# 01_MAIN.net
KiCad netlist of a schematic drawn in Altium Designer
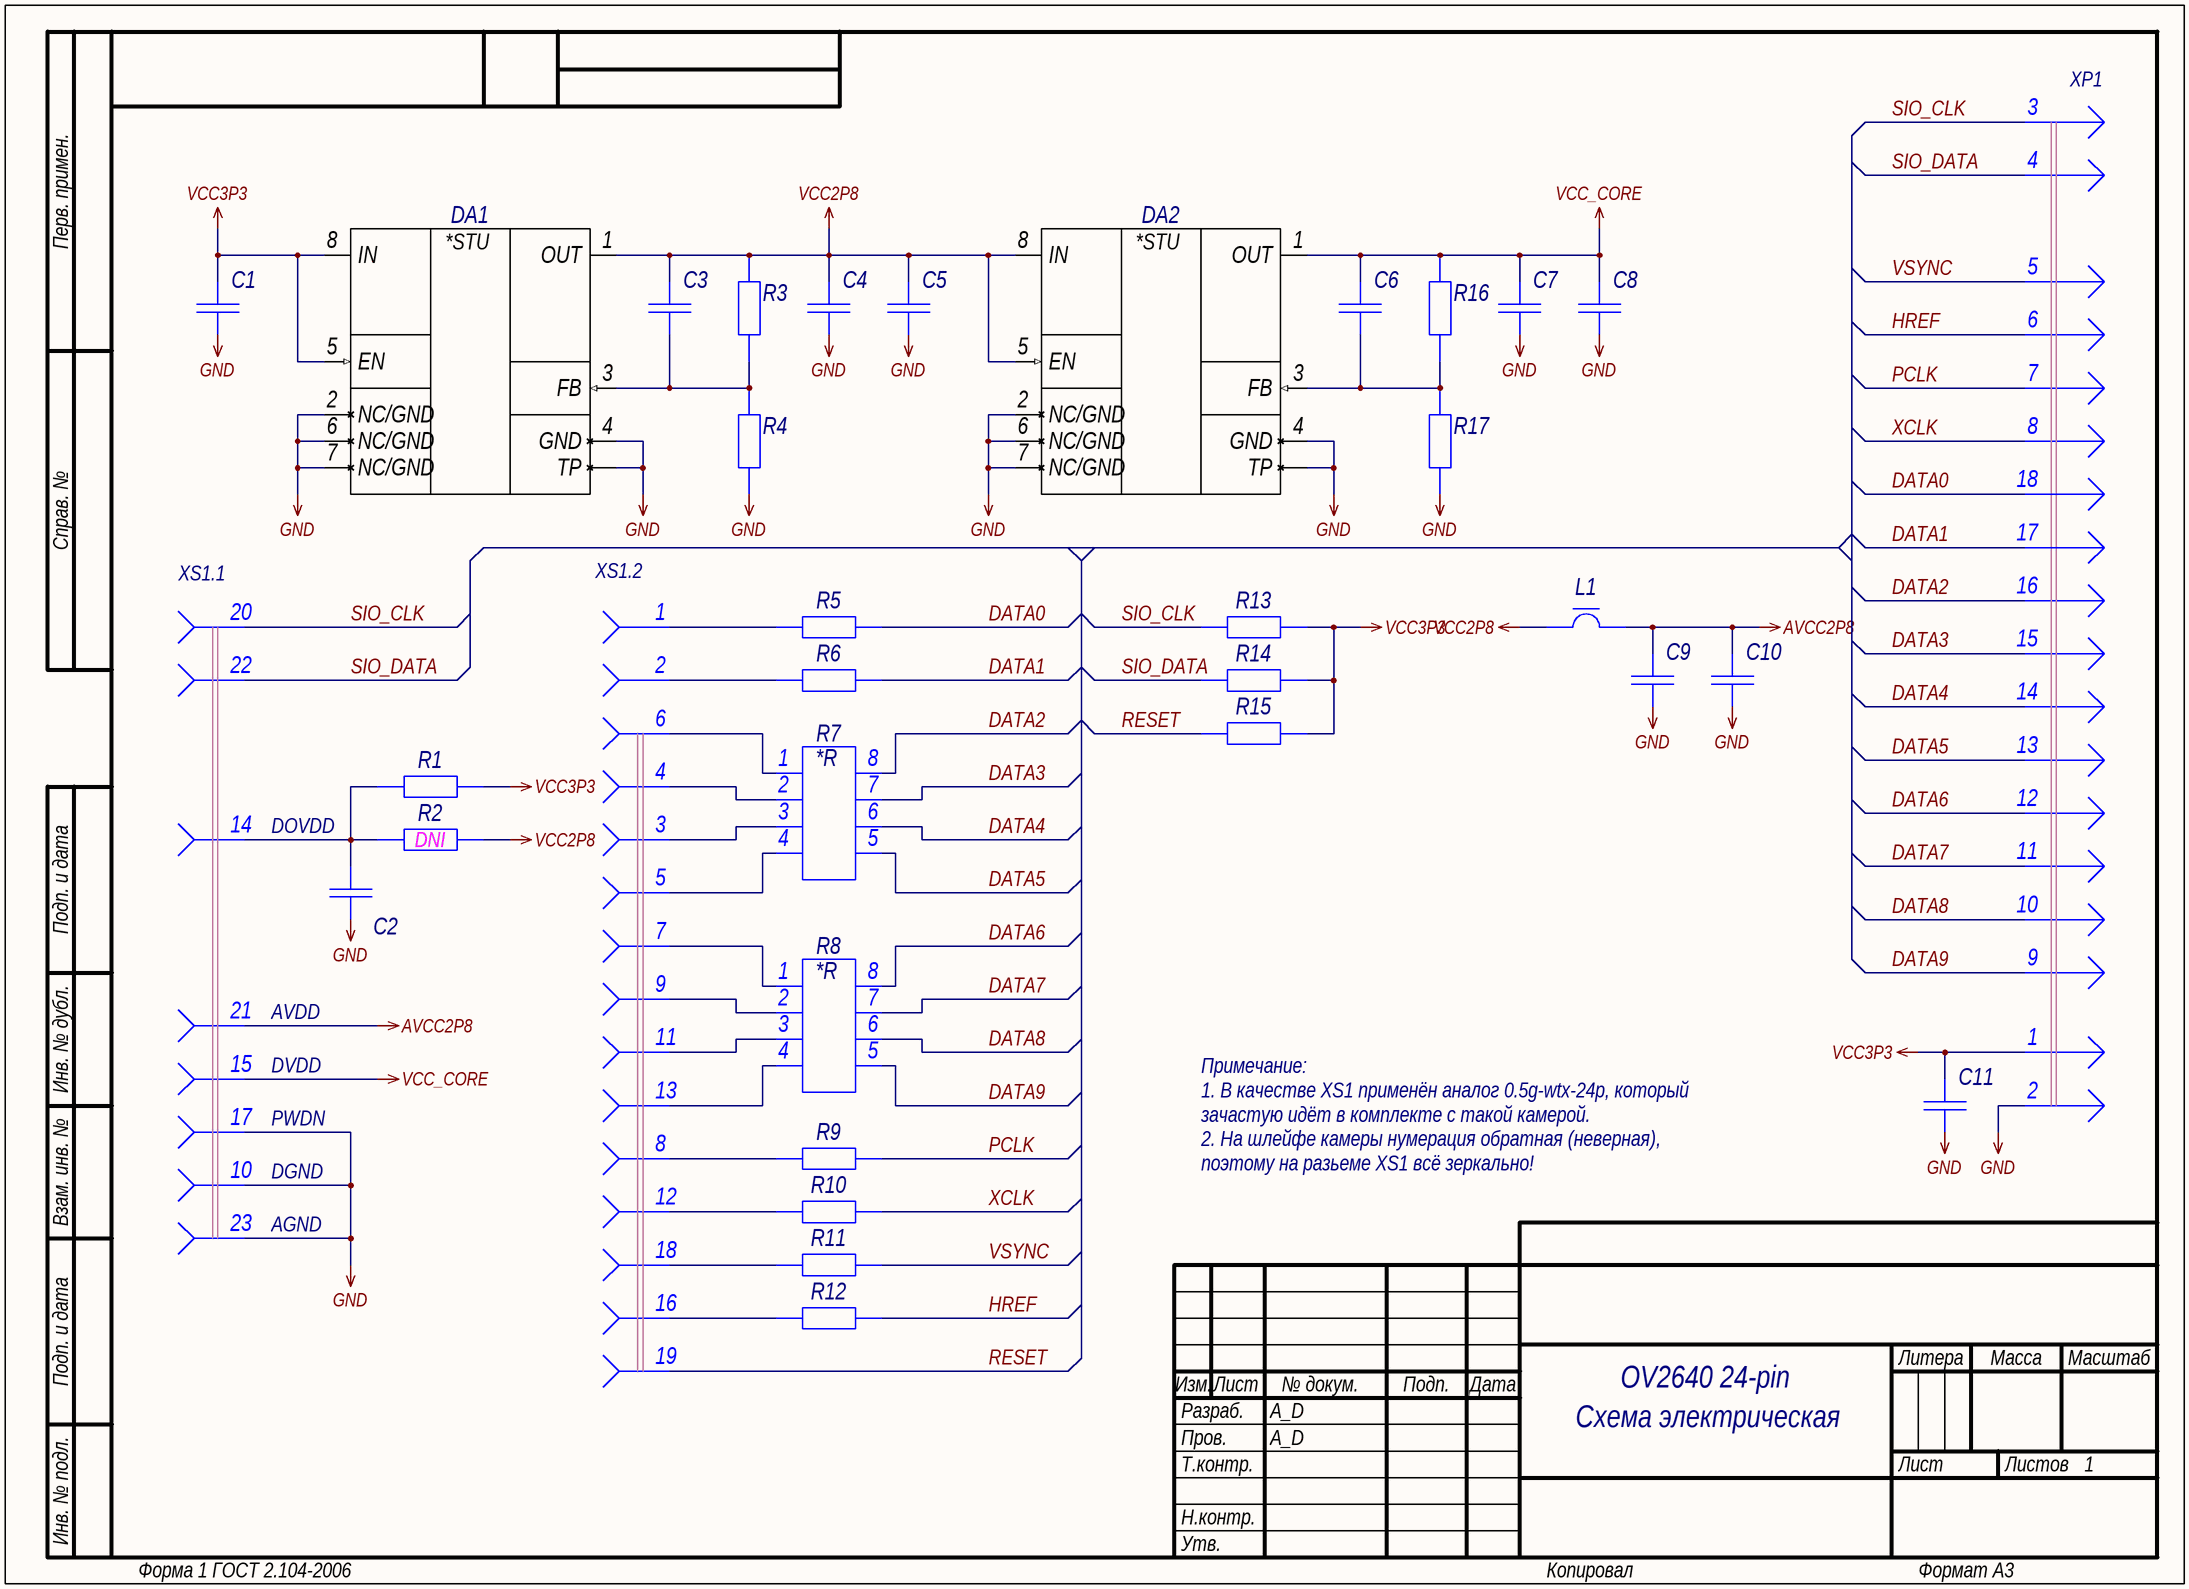
[diagram p0: 01_MAIN.SchDoc]

(export (version "E")
  (design (tool "Eeschema 10.0.6"))
  (components
    (comp (ref "C1")
      (value "Capacitor")
      (footprint "C0603_160X080H080_H")
      (fields
        (field (name "PART NUMBER") "GCM188R71E105KA64D")
        (field (name "VOLTAGE") "25V")
        (field (name "TOLERANCE") "±10%")
        (field (name "PUBLISHER") "Andrew Danich")
      )
      (libsource (lib "ADLib") (part "Capacitor"))
    )
    (comp (ref "C2")
      (value "Capacitor")
      (footprint "C0603_160X080H080_H")
      (fields
        (field (name "PART NUMBER") "GCM188R71E105KA64D")
        (field (name "VOLTAGE") "25V")
        (field (name "TOLERANCE") "±10%")
        (field (name "PUBLISHER") "Andrew Danich")
      )
      (libsource (lib "ADLib") (part "Capacitor"))
    )
    (comp (ref "C3")
      (value "Capacitor")
      (footprint "C0603_160X080H080_H")
      (fields
        (field (name "PART NUMBER") "GRM1885C1H270JA01D")
        (field (name "VOLTAGE") "50V")
        (field (name "TOLERANCE") "±5%")
        (field (name "PUBLISHER") "Andrew Danich")
      )
      (libsource (lib "ADLib") (part "Capacitor"))
    )
    (comp (ref "C4")
      (value "Capacitor")
      (footprint "C0603_160X080H080_H")
      (fields
        (field (name "PART NUMBER") "GRM188R60J106ME47D")
        (field (name "VOLTAGE") "6.3V")
        (field (name "TOLERANCE") "±20%")
        (field (name "PUBLISHER") "Andrew Danich")
      )
      (libsource (lib "ADLib") (part "Capacitor"))
    )
    (comp (ref "C5")
      (value "Capacitor")
      (footprint "C0603_160X080H080_H")
      (fields
        (field (name "PART NUMBER") "GCM188R71E105KA64D")
        (field (name "VOLTAGE") "25V")
        (field (name "TOLERANCE") "±10%")
        (field (name "PUBLISHER") "Andrew Danich")
      )
      (libsource (lib "ADLib") (part "Capacitor"))
    )
    (comp (ref "C6")
      (value "Capacitor")
      (footprint "C0603_160X080H080_H")
      (fields
        (field (name "PART NUMBER") "GRM1885C1H270JA01D")
        (field (name "VOLTAGE") "50V")
        (field (name "TOLERANCE") "±5%")
        (field (name "PUBLISHER") "Andrew Danich")
      )
      (libsource (lib "ADLib") (part "Capacitor"))
    )
    (comp (ref "C7")
      (value "Capacitor")
      (footprint "C0603_160X080H080_H")
      (fields
        (field (name "PART NUMBER") "GRM188R60J106ME47D")
        (field (name "VOLTAGE") "6.3V")
        (field (name "TOLERANCE") "±20%")
        (field (name "PUBLISHER") "Andrew Danich")
      )
      (libsource (lib "ADLib") (part "Capacitor"))
    )
    (comp (ref "C8")
      (value "Capacitor")
      (footprint "C0603_160X080H080_H")
      (fields
        (field (name "PART NUMBER") "GRM188R72A104KA35D")
        (field (name "VOLTAGE") "100V")
        (field (name "TOLERANCE") "±10%")
        (field (name "PUBLISHER") "Andrew Danich")
      )
      (libsource (lib "ADLib") (part "Capacitor"))
    )
    (comp (ref "C9")
      (value "Capacitor")
      (footprint "C0603_160X080H080_H")
      (fields
        (field (name "PART NUMBER") "GCM188R71E105KA64D")
        (field (name "VOLTAGE") "25V")
        (field (name "TOLERANCE") "±10%")
        (field (name "PUBLISHER") "Andrew Danich")
      )
      (libsource (lib "ADLib") (part "Capacitor"))
    )
    (comp (ref "C10")
      (value "Capacitor")
      (footprint "C0603_160X080H080_H")
      (fields
        (field (name "PART NUMBER") "GRM188R72A104KA35D")
        (field (name "VOLTAGE") "100V")
        (field (name "TOLERANCE") "±10%")
        (field (name "PUBLISHER") "Andrew Danich")
      )
      (libsource (lib "ADLib") (part "Capacitor"))
    )
    (comp (ref "C11")
      (value "Capacitor")
      (footprint "C0603_160X080H080_H")
      (fields
        (field (name "PART NUMBER") "GRM188R60J106ME47D")
        (field (name "VOLTAGE") "6.3V")
        (field (name "TOLERANCE") "±20%")
        (field (name "PUBLISHER") "Andrew Danich")
      )
      (libsource (lib "ADLib") (part "Capacitor"))
    )
    (comp (ref "DA1")
      (value "TPS73501DRB")
      (footprint "VSON-8_065P300X300X100_N")
      (fields
        (field (name "PART NUMBER") "TPS73501DRBR")
        (field (name "MANUFACTURER") "Texas Instruments")
        (field (name "PUBLISHER") "Andrew Danich")
      )
      (libsource (lib "ADLib") (part "TPS73501DRB"))
    )
    (comp (ref "DA2")
      (value "TPS73501DRB")
      (footprint "VSON-8_065P300X300X100_N")
      (fields
        (field (name "PART NUMBER") "TPS73501DRBR")
        (field (name "MANUFACTURER") "Texas Instruments")
        (field (name "PUBLISHER") "Andrew Danich")
      )
      (libsource (lib "ADLib") (part "TPS73501DRB"))
    )
    (comp (ref "L1")
      (value "FerriteBead")
      (footprint "L0603_160X080H080_H")
      (fields
        (field (name "PART NUMBER") "BLM18PG221SH1D")
        (field (name "TOLERANCE") "±25%")
        (field (name "MANUFACTURER") "Murata")
        (field (name "PUBLISHER") "Andrew Danich")
      )
      (libsource (lib "ADLib") (part "FerriteBead"))
    )
    (comp (ref "R1")
      (value "Resistor")
      (footprint "R0603_160X080H045_H")
      (fields
        (field (name "PART NUMBER") "RC0603JR-070R")
        (field (name "TOLERANCE") "±5%")
        (field (name "MANUFACTURER") "Yageo")
        (field (name "PUBLISHER") "Andrew Danich")
      )
      (libsource (lib "ADLib") (part "Resistor"))
    )
    (comp (ref "R2")
      (value "Resistor")
      (footprint "R0603_160X080H045_H")
      (fields
        (field (name "PART NUMBER") "RC0603JR-070R")
        (field (name "TOLERANCE") "±5%")
        (field (name "MANUFACTURER") "Yageo")
        (field (name "PUBLISHER") "Andrew Danich")
      )
      (libsource (lib "ADLib") (part "Resistor"))
    )
    (comp (ref "R3")
      (value "Resistor")
      (footprint "R0603_160X080H045_H")
      (fields
        (field (name "PART NUMBER") "RC0603JR-0727KL")
        (field (name "TOLERANCE") "±5%")
        (field (name "MANUFACTURER") "Yageo")
        (field (name "PUBLISHER") "Andrew Danich")
      )
      (libsource (lib "ADLib") (part "Resistor"))
    )
    (comp (ref "R4")
      (value "Resistor")
      (footprint "R0603_160X080H045_H")
      (fields
        (field (name "PART NUMBER") "RC0603FR-0720KL")
        (field (name "TOLERANCE") "±1%")
        (field (name "MANUFACTURER") "Yageo")
        (field (name "PUBLISHER") "Andrew Danich")
      )
      (libsource (lib "ADLib") (part "Resistor"))
    )
    (comp (ref "R5")
      (value "Resistor")
      (footprint "R0603_160X080H045_H")
      (fields
        (field (name "PART NUMBER") "RC0603JR-0751RL")
        (field (name "TOLERANCE") "±5%")
        (field (name "MANUFACTURER") "Yageo")
        (field (name "PUBLISHER") "Andrew Danich")
      )
      (libsource (lib "ADLib") (part "Resistor"))
    )
    (comp (ref "R6")
      (value "Resistor")
      (footprint "R0603_160X080H045_H")
      (fields
        (field (name "PART NUMBER") "RC0603JR-0751RL")
        (field (name "TOLERANCE") "±5%")
        (field (name "MANUFACTURER") "Yageo")
        (field (name "PUBLISHER") "Andrew Danich")
      )
      (libsource (lib "ADLib") (part "Resistor"))
    )
    (comp (ref "R7")
      (value "Resistor-4")
      (footprint "CAT16-x4")
      (fields
        (field (name "PART NUMBER") "CAT16-510J4LF")
        (field (name "TOLERANCE") "±5%")
        (field (name "MANUFACTURER") "Bourns")
        (field (name "PUBLISHER") "Andrew Danich")
      )
      (libsource (lib "ADLib") (part "Resistor-4"))
    )
    (comp (ref "R8")
      (value "Resistor-4")
      (footprint "CAT16-x4")
      (fields
        (field (name "PART NUMBER") "CAT16-510J4LF")
        (field (name "TOLERANCE") "±5%")
        (field (name "MANUFACTURER") "Bourns")
        (field (name "PUBLISHER") "Andrew Danich")
      )
      (libsource (lib "ADLib") (part "Resistor-4"))
    )
    (comp (ref "R9")
      (value "Resistor")
      (footprint "R0603_160X080H045_H")
      (fields
        (field (name "PART NUMBER") "RC0603JR-0751RL")
        (field (name "TOLERANCE") "±5%")
        (field (name "MANUFACTURER") "Yageo")
        (field (name "PUBLISHER") "Andrew Danich")
      )
      (libsource (lib "ADLib") (part "Resistor"))
    )
    (comp (ref "R10")
      (value "Resistor")
      (footprint "R0603_160X080H045_H")
      (fields
        (field (name "PART NUMBER") "RC0603JR-0751RL")
        (field (name "TOLERANCE") "±5%")
        (field (name "MANUFACTURER") "Yageo")
        (field (name "PUBLISHER") "Andrew Danich")
      )
      (libsource (lib "ADLib") (part "Resistor"))
    )
    (comp (ref "R11")
      (value "Resistor")
      (footprint "R0603_160X080H045_H")
      (fields
        (field (name "PART NUMBER") "RC0603JR-0751RL")
        (field (name "TOLERANCE") "±5%")
        (field (name "MANUFACTURER") "Yageo")
        (field (name "PUBLISHER") "Andrew Danich")
      )
      (libsource (lib "ADLib") (part "Resistor"))
    )
    (comp (ref "R12")
      (value "Resistor")
      (footprint "R0603_160X080H045_H")
      (fields
        (field (name "PART NUMBER") "RC0603JR-0751RL")
        (field (name "TOLERANCE") "±5%")
        (field (name "MANUFACTURER") "Yageo")
        (field (name "PUBLISHER") "Andrew Danich")
      )
      (libsource (lib "ADLib") (part "Resistor"))
    )
    (comp (ref "R13")
      (value "Resistor")
      (footprint "R0603_160X080H045_H")
      (fields
        (field (name "PART NUMBER") "RC0603JR-074K7L")
        (field (name "TOLERANCE") "±5%")
        (field (name "MANUFACTURER") "Yageo")
        (field (name "PUBLISHER") "Andrew Danich")
      )
      (libsource (lib "ADLib") (part "Resistor"))
    )
    (comp (ref "R14")
      (value "Resistor")
      (footprint "R0603_160X080H045_H")
      (fields
        (field (name "PART NUMBER") "RC0603JR-074K7L")
        (field (name "TOLERANCE") "±5%")
        (field (name "MANUFACTURER") "Yageo")
        (field (name "PUBLISHER") "Andrew Danich")
      )
      (libsource (lib "ADLib") (part "Resistor"))
    )
    (comp (ref "R15")
      (value "Resistor")
      (footprint "R0603_160X080H045_H")
      (fields
        (field (name "PART NUMBER") "RC0603JR-074K7L")
        (field (name "TOLERANCE") "±5%")
        (field (name "MANUFACTURER") "Yageo")
        (field (name "PUBLISHER") "Andrew Danich")
      )
      (libsource (lib "ADLib") (part "Resistor"))
    )
    (comp (ref "R16")
      (value "Resistor")
      (footprint "R0603_160X080H045_H")
      (fields
        (field (name "PART NUMBER") "RC0603JR-0727KL")
        (field (name "TOLERANCE") "±5%")
        (field (name "MANUFACTURER") "Yageo")
        (field (name "PUBLISHER") "Andrew Danich")
      )
      (libsource (lib "ADLib") (part "Resistor"))
    )
    (comp (ref "R17")
      (value "Resistor")
      (footprint "R0603_160X080H045_H")
      (fields
        (field (name "PART NUMBER") "RC0603JR-07360KL")
        (field (name "TOLERANCE") "±5%")
        (field (name "MANUFACTURER") "Yageo")
        (field (name "PUBLISHER") "Andrew Danich")
      )
      (libsource (lib "ADLib") (part "Resistor"))
    )
    (comp (ref "XP1")
      (value "Text")
      (footprint "PLD-18")
      (fields (field (name "PART NUMBER") "PLD-18") (field (name "PUBLISHER") "Andrew Danich"))
      (libsource (lib "ADLib") (part "Con-18-M_S"))
    )
    (comp (ref "XS1")
      (value "OV7670")
      (footprint "FH12-24S-0.5SH")
      (fields
        (field (name "PART NUMBER") "FH12-24S-0.5SH(55)")
        (field (name "MANUFACTURER") "Hirose Connector")
        (field (name "PUBLISHER") "Andrew Danich")
      )
      (libsource (lib "ADLib") (part "Con-24-F_S"))
    )
  )
  (nets
    (net (code "1") (name "/DATA0") (class "Default")
      (node (ref "R5") (pin "2") (pinfunction "2_2") (pintype "passive"))
      (node (ref "XP1") (pin "18") (pintype "passive"))
    )
    (net (code "2") (name "/DATA1") (class "Default")
      (node (ref "R6") (pin "2") (pinfunction "2_2") (pintype "passive"))
      (node (ref "XP1") (pin "17") (pintype "passive"))
    )
    (net (code "3") (name "/DATA2") (class "Default")
      (node (ref "R7") (pin "8") (pintype "passive"))
      (node (ref "XP1") (pin "16") (pintype "passive"))
    )
    (net (code "4") (name "/DATA3") (class "Default")
      (node (ref "R7") (pin "7") (pintype "passive"))
      (node (ref "XP1") (pin "15") (pintype "passive"))
    )
    (net (code "5") (name "/DATA4") (class "Default")
      (node (ref "R7") (pin "6") (pintype "passive"))
      (node (ref "XP1") (pin "14") (pintype "passive"))
    )
    (net (code "6") (name "/DATA5") (class "Default")
      (node (ref "R7") (pin "5") (pintype "passive"))
      (node (ref "XP1") (pin "13") (pintype "passive"))
    )
    (net (code "7") (name "/DATA6") (class "Default")
      (node (ref "R8") (pin "8") (pintype "passive"))
      (node (ref "XP1") (pin "12") (pintype "passive"))
    )
    (net (code "8") (name "/DATA7") (class "Default")
      (node (ref "R8") (pin "7") (pintype "passive"))
      (node (ref "XP1") (pin "11") (pintype "passive"))
    )
    (net (code "9") (name "/DATA8") (class "Default")
      (node (ref "R8") (pin "6") (pintype "passive"))
      (node (ref "XP1") (pin "10") (pintype "passive"))
    )
    (net (code "10") (name "/DATA9") (class "Default")
      (node (ref "R8") (pin "5") (pintype "passive"))
      (node (ref "XP1") (pin "9") (pintype "passive"))
    )
    (net (code "11") (name "/HREF") (class "Default")
      (node (ref "R12") (pin "2") (pinfunction "2_2") (pintype "passive"))
      (node (ref "XP1") (pin "6") (pintype "passive"))
    )
    (net (code "12") (name "/PCLK") (class "Default")
      (node (ref "R9") (pin "2") (pinfunction "2_2") (pintype "passive"))
      (node (ref "XP1") (pin "7") (pintype "passive"))
    )
    (net (code "13") (name "/RESET") (class "Default")
      (node (ref "R15") (pin "1") (pinfunction "1_1") (pintype "passive"))
      (node (ref "XS1") (pin "19") (pintype "passive"))
    )
    (net (code "14") (name "/SIO_CLK") (class "Default")
      (node (ref "R13") (pin "1") (pinfunction "1_1") (pintype "passive"))
      (node (ref "XP1") (pin "3") (pintype "passive"))
      (node (ref "XS1") (pin "20") (pintype "passive"))
    )
    (net (code "15") (name "/SIO_DATA") (class "Default")
      (node (ref "R14") (pin "1") (pinfunction "1_1") (pintype "passive"))
      (node (ref "XP1") (pin "4") (pintype "passive"))
      (node (ref "XS1") (pin "22") (pintype "passive"))
    )
    (net (code "16") (name "/VSYNC") (class "Default")
      (node (ref "R11") (pin "2") (pinfunction "2_2") (pintype "passive"))
      (node (ref "XP1") (pin "5") (pintype "passive"))
    )
    (net (code "17") (name "/XCLK") (class "Default")
      (node (ref "R10") (pin "2") (pinfunction "2_2") (pintype "passive"))
      (node (ref "XP1") (pin "8") (pintype "passive"))
    )
    (net (code "18") (name "AVCC2P8") (class "Default")
      (node (ref "C10") (pin "2") (pinfunction "2_2") (pintype "passive"))
      (node (ref "C9") (pin "2") (pinfunction "2_2") (pintype "passive"))
      (node (ref "L1") (pin "2") (pinfunction "2_2") (pintype "passive"))
      (node (ref "XS1") (pin "21") (pintype "passive"))
    )
    (net (code "19") (name "GND") (class "Default")
      (node (ref "C1") (pin "1") (pinfunction "1_1") (pintype "passive"))
      (node (ref "C10") (pin "1") (pinfunction "1_1") (pintype "passive"))
      (node (ref "C11") (pin "1") (pinfunction "1_1") (pintype "passive"))
      (node (ref "C2") (pin "1") (pinfunction "1_1") (pintype "passive"))
      (node (ref "C4") (pin "1") (pinfunction "1_1") (pintype "passive"))
      (node (ref "C5") (pin "1") (pinfunction "1_1") (pintype "passive"))
      (node (ref "C7") (pin "1") (pinfunction "1_1") (pintype "passive"))
      (node (ref "C8") (pin "1") (pinfunction "1_1") (pintype "passive"))
      (node (ref "C9") (pin "1") (pinfunction "1_1") (pintype "passive"))
      (node (ref "DA1") (pin "2") (pinfunction "NC/GND_2") (pintype "passive"))
      (node (ref "DA1") (pin "4") (pinfunction "GND_4") (pintype "power_in"))
      (node (ref "DA1") (pin "6") (pinfunction "NC/GND_6") (pintype "passive"))
      (node (ref "DA1") (pin "7") (pinfunction "NC/GND_7") (pintype "passive"))
      (node (ref "DA1") (pin "TP") (pinfunction "TP_TP") (pintype "passive"))
      (node (ref "DA2") (pin "2") (pinfunction "NC/GND_2") (pintype "passive"))
      (node (ref "DA2") (pin "4") (pinfunction "GND_4") (pintype "power_in"))
      (node (ref "DA2") (pin "6") (pinfunction "NC/GND_6") (pintype "passive"))
      (node (ref "DA2") (pin "7") (pinfunction "NC/GND_7") (pintype "passive"))
      (node (ref "DA2") (pin "TP") (pinfunction "TP_TP") (pintype "passive"))
      (node (ref "R17") (pin "1") (pinfunction "1_1") (pintype "passive"))
      (node (ref "R4") (pin "1") (pinfunction "1_1") (pintype "passive"))
      (node (ref "XP1") (pin "2") (pintype "passive"))
      (node (ref "XS1") (pin "10") (pintype "passive"))
      (node (ref "XS1") (pin "17") (pintype "passive"))
      (node (ref "XS1") (pin "23") (pintype "passive"))
    )
    (net (code "20") (name "Net-(C2-Pad2)") (class "Default")
      (node (ref "C2") (pin "2") (pinfunction "2_2") (pintype "passive"))
      (node (ref "R1") (pin "1") (pinfunction "1_1") (pintype "passive"))
      (node (ref "R2") (pin "1") (pinfunction "1_1") (pintype "passive"))
      (node (ref "XS1") (pin "14") (pintype "passive"))
    )
    (net (code "21") (name "Net-(DA1-FB)") (class "Default")
      (node (ref "C3") (pin "1") (pinfunction "1_1") (pintype "passive"))
      (node (ref "DA1") (pin "3") (pinfunction "FB_3") (pintype "input"))
      (node (ref "R3") (pin "2") (pinfunction "2_2") (pintype "passive"))
      (node (ref "R4") (pin "2") (pinfunction "2_2") (pintype "passive"))
    )
    (net (code "22") (name "Net-(DA2-FB)") (class "Default")
      (node (ref "C6") (pin "1") (pinfunction "1_1") (pintype "passive"))
      (node (ref "DA2") (pin "3") (pinfunction "FB_3") (pintype "input"))
      (node (ref "R16") (pin "1") (pinfunction "1_1") (pintype "passive"))
      (node (ref "R17") (pin "2") (pinfunction "2_2") (pintype "passive"))
    )
    (net (code "23") (name "Net-(R5-Pad1)") (class "Default")
      (node (ref "R5") (pin "1") (pinfunction "1_1") (pintype "passive"))
      (node (ref "XS1") (pin "1") (pintype "passive"))
    )
    (net (code "24") (name "Net-(R6-Pad1)") (class "Default")
      (node (ref "R6") (pin "1") (pinfunction "1_1") (pintype "passive"))
      (node (ref "XS1") (pin "2") (pintype "passive"))
    )
    (net (code "25") (name "Net-(R7-Pad1)") (class "Default")
      (node (ref "R7") (pin "1") (pintype "passive"))
      (node (ref "XS1") (pin "6") (pintype "passive"))
    )
    (net (code "26") (name "Net-(R7-Pad2)") (class "Default")
      (node (ref "R7") (pin "2") (pintype "passive"))
      (node (ref "XS1") (pin "4") (pintype "passive"))
    )
    (net (code "27") (name "Net-(R7-Pad3)") (class "Default")
      (node (ref "R7") (pin "3") (pintype "passive"))
      (node (ref "XS1") (pin "3") (pintype "passive"))
    )
    (net (code "28") (name "Net-(R7-Pad4)") (class "Default")
      (node (ref "R7") (pin "4") (pintype "passive"))
      (node (ref "XS1") (pin "5") (pintype "passive"))
    )
    (net (code "29") (name "Net-(R8-Pad1)") (class "Default")
      (node (ref "R8") (pin "1") (pintype "passive"))
      (node (ref "XS1") (pin "7") (pintype "passive"))
    )
    (net (code "30") (name "Net-(R8-Pad2)") (class "Default")
      (node (ref "R8") (pin "2") (pintype "passive"))
      (node (ref "XS1") (pin "9") (pintype "passive"))
    )
    (net (code "31") (name "Net-(R8-Pad3)") (class "Default")
      (node (ref "R8") (pin "3") (pintype "passive"))
      (node (ref "XS1") (pin "11") (pintype "passive"))
    )
    (net (code "32") (name "Net-(R8-Pad4)") (class "Default")
      (node (ref "R8") (pin "4") (pintype "passive"))
      (node (ref "XS1") (pin "13") (pintype "passive"))
    )
    (net (code "33") (name "Net-(R9-Pad1)") (class "Default")
      (node (ref "R9") (pin "1") (pinfunction "1_1") (pintype "passive"))
      (node (ref "XS1") (pin "8") (pintype "passive"))
    )
    (net (code "34") (name "Net-(R10-Pad1)") (class "Default")
      (node (ref "R10") (pin "1") (pinfunction "1_1") (pintype "passive"))
      (node (ref "XS1") (pin "12") (pintype "passive"))
    )
    (net (code "35") (name "Net-(R11-Pad1)") (class "Default")
      (node (ref "R11") (pin "1") (pinfunction "1_1") (pintype "passive"))
      (node (ref "XS1") (pin "18") (pintype "passive"))
    )
    (net (code "36") (name "Net-(R12-Pad1)") (class "Default")
      (node (ref "R12") (pin "1") (pinfunction "1_1") (pintype "passive"))
      (node (ref "XS1") (pin "16") (pintype "passive"))
    )
    (net (code "37") (name "VCC2P8") (class "Default")
      (node (ref "C3") (pin "2") (pinfunction "2_2") (pintype "passive"))
      (node (ref "C4") (pin "2") (pinfunction "2_2") (pintype "passive"))
      (node (ref "C5") (pin "2") (pinfunction "2_2") (pintype "passive"))
      (node (ref "DA1") (pin "1") (pinfunction "OUT_1") (pintype "power_in"))
      (node (ref "DA2") (pin "5") (pinfunction "EN_5") (pintype "input"))
      (node (ref "DA2") (pin "8") (pinfunction "IN_8") (pintype "power_in"))
      (node (ref "L1") (pin "1") (pinfunction "1_1") (pintype "passive"))
      (node (ref "R2") (pin "2") (pinfunction "2_2") (pintype "passive"))
      (node (ref "R3") (pin "1") (pinfunction "1_1") (pintype "passive"))
    )
    (net (code "38") (name "VCC3P3") (class "Default")
      (node (ref "C1") (pin "2") (pinfunction "2_2") (pintype "passive"))
      (node (ref "C11") (pin "2") (pinfunction "2_2") (pintype "passive"))
      (node (ref "DA1") (pin "5") (pinfunction "EN_5") (pintype "input"))
      (node (ref "DA1") (pin "8") (pinfunction "IN_8") (pintype "power_in"))
      (node (ref "R1") (pin "2") (pinfunction "2_2") (pintype "passive"))
      (node (ref "R13") (pin "2") (pinfunction "2_2") (pintype "passive"))
      (node (ref "R14") (pin "2") (pinfunction "2_2") (pintype "passive"))
      (node (ref "R15") (pin "2") (pinfunction "2_2") (pintype "passive"))
      (node (ref "XP1") (pin "1") (pintype "passive"))
    )
    (net (code "39") (name "VCC_CORE") (class "Default")
      (node (ref "C6") (pin "2") (pinfunction "2_2") (pintype "passive"))
      (node (ref "C7") (pin "2") (pinfunction "2_2") (pintype "passive"))
      (node (ref "C8") (pin "2") (pinfunction "2_2") (pintype "passive"))
      (node (ref "DA2") (pin "1") (pinfunction "OUT_1") (pintype "power_in"))
      (node (ref "R16") (pin "2") (pinfunction "2_2") (pintype "passive"))
      (node (ref "XS1") (pin "15") (pintype "passive"))
    )
  )
)
